# microcontroller.net
KiCad netlist of a schematic drawn in Altium Designer
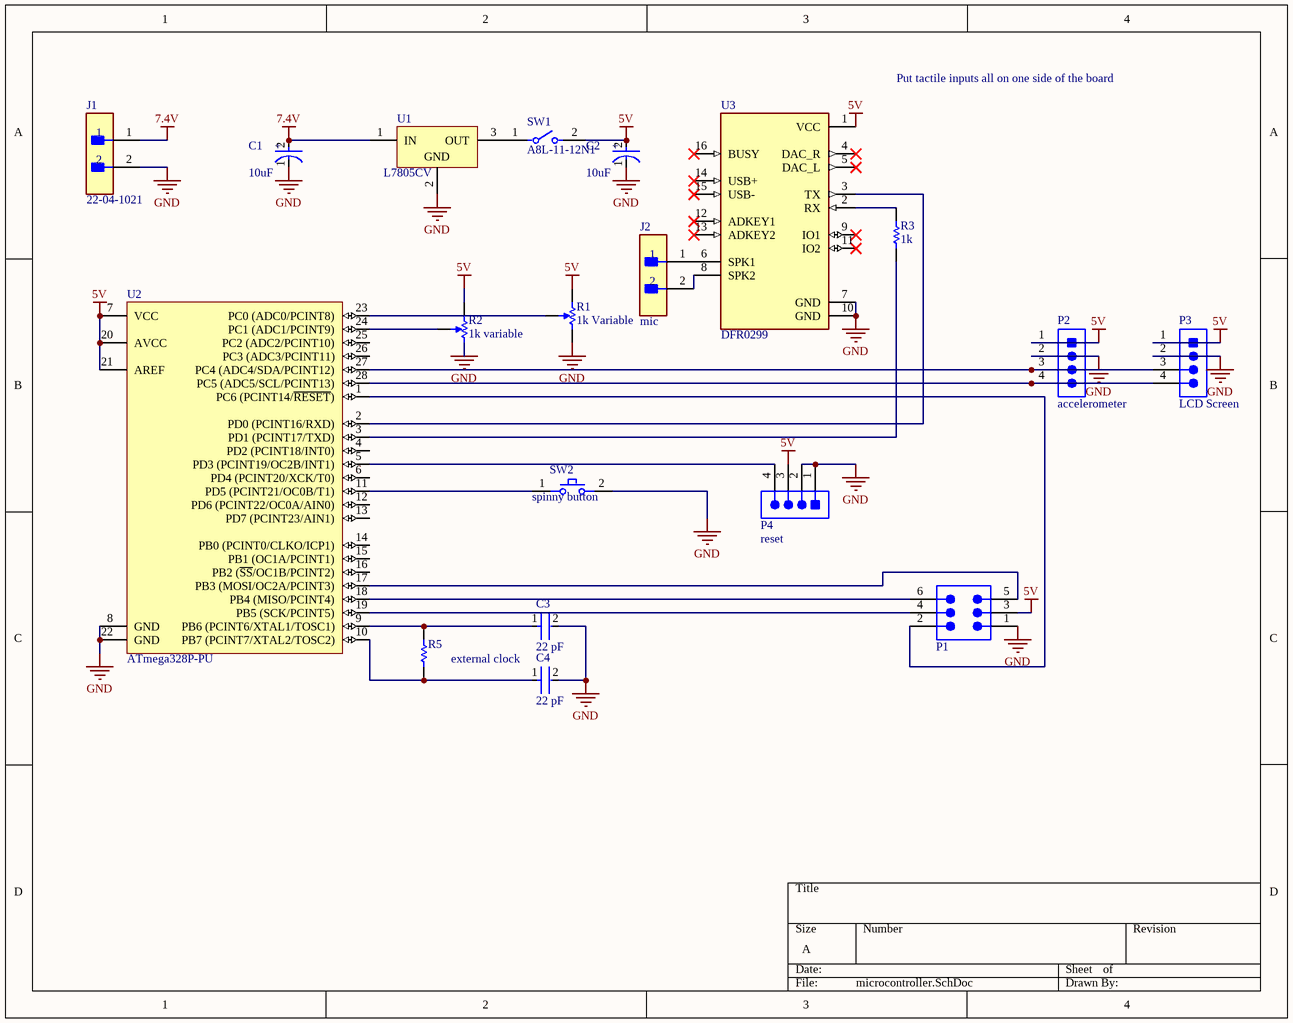
[diagram p0: microcontroller.SchDoc]

(export (version "E")
  (design (tool "Eeschema 10.0.6"))
  (components
    (comp (ref "C1")
      (value "10uF")
      (footprint "FP-RAD-TH-D_16_0_5-L_15_1-MFG")
      (description "Aluminum Electrolytic Capacitors (Radial Lead Type) AEC-Q200 Qualified 330uF ±20% 50V")
      (fields (field (name "TOLERANCE") "20%"))
      (libsource (lib "Altium Content Vault") (part "a00bbbee19879c290e62620ae7e47b1"))
    )
    (comp (ref "C2")
      (value "10uF")
      (footprint "FP-RAD-TH-D_16_0_5-L_15_1-MFG")
      (description "Aluminum Electrolytic Capacitors (Radial Lead Type) AEC-Q200 Qualified 330uF ±20% 50V")
      (fields (field (name "TOLERANCE") "20%"))
      (libsource (lib "Altium Content Vault") (part "a00bbbee19879c290e62620ae7e47b1"))
    )
    (comp (ref "C3")
      (value "22 pF")
      (footprint "FP-DE1_D9_T4_F10_d0_6-0_0-MFG")
      (description "Cap Ceramic Disc 2200pF 20% 250VAC Thru-Hole 9.0x4.0x10.0 Ammo pack")
      (fields (field (name "TOLERANCE") "20%"))
      (libsource (lib "Altium Content Vault") (part "11868f565c42a9108669ba33697ecf6"))
    )
    (comp (ref "C4")
      (value "22 pF")
      (footprint "FP-DE1_D9_T4_F10_d0_6-0_0-MFG")
      (description "Cap Ceramic Disc 2200pF 20% 250VAC Thru-Hole 9.0x4.0x10.0 Ammo pack")
      (fields (field (name "TOLERANCE") "20%"))
      (libsource (lib "Altium Content Vault") (part "11868f565c42a9108669ba33697ecf6"))
    )
    (comp (ref "J1")
      (value "22-04-1021")
      (footprint "FP-22-04-1021-MFG")
      (description "CONN HEADER VERT 2POS 2.5MM")
      (libsource (lib "Altium Content Vault") (part "3bc925449376181038e59eaffc5286c"))
    )
    (comp (ref "J2")
      (value "mic")
      (footprint "FP-22-04-1021-MFG")
      (description "CONN HEADER VERT 2POS 2.5MM")
      (libsource (lib "Altium Content Vault") (part "3bc925449376181038e59eaffc5286c"))
    )
    (comp (ref "P1")
      (value "61200621621")
      (footprint "61200621621")
      (description "WR-BHD Male Box Header, THT Straight, pitch 2.54mm, 2 row, 6 pin")
      (fields (field (name "MANUFACTURER") "Wurth Elektronik"))
      (libsource (lib "Altium_WR-BHD_rev22c") (part "61200621621"))
    )
    (comp (ref "P2")
      (value "accelerometer")
      (footprint "MOLX-22-27-2041_V")
      (description "Male Header, Pitch 2.54 mm, 1 x 4 Position, Height 11.7 mm, Tail Length 3.56 mm, RoHS, Bulk")
      (fields (field (name "MANUFACTURER") "Molex"))
      (libsource (lib "Altium Content Vault") (part "CN-1P-M-R4"))
    )
    (comp (ref "P3")
      (value "LCD Screen")
      (footprint "MOLX-22-27-2041_V")
      (description "Male Header, Pitch 2.54 mm, 1 x 4 Position, Height 11.7 mm, Tail Length 3.56 mm, RoHS, Bulk")
      (fields (field (name "MANUFACTURER") "Molex"))
      (libsource (lib "Altium Content Vault") (part "CN-1P-M-R4"))
    )
    (comp (ref "P4")
      (value "reset")
      (footprint "MOLX-22-27-2041_V")
      (description "Male Header, Pitch 2.54 mm, 1 x 4 Position, Height 11.7 mm, Tail Length 3.56 mm, RoHS, Bulk")
      (fields (field (name "MANUFACTURER") "Molex"))
      (libsource (lib "") (part "CN-1P-M-R4_1"))
    )
    (comp (ref "R1")
      (value "1k Variable")
      (footprint "BIT-93PR1KLF")
      (fields (field (name "MANUFACTURER") "BI Technologies"))
      (libsource (lib "Altium Content Vault") (part "RES-ADJ-3_A"))
    )
    (comp (ref "R2")
      (value "1k variable")
      (footprint "BIT-93PR1KLF")
      (fields (field (name "MANUFACTURER") "BI Technologies"))
      (libsource (lib "Altium Content Vault") (part "RES-ADJ-3_A"))
    )
    (comp (ref "R3")
      (value "1k")
      (footprint "RESA60-630X240")
      (description "Axial Resistor, 1 KOhm, +/- 1%, 250 mW, -55 to 155 degC, 2-Pin THD, RoHS, Bulk")
      (fields (field (name "TOLERANCE") "1%"))
      (libsource (lib "Altium Content Vault") (part "RES-2"))
    )
    (comp (ref "R5")
      (value "external clock")
      (footprint "RESA60-630X240")
      (description "Axial Resistor, 1 KOhm, +/- 1%, 250 mW, -55 to 155 degC, 2-Pin THD, RoHS, Bulk")
      (fields (field (name "TOLERANCE") "1%"))
      (libsource (lib "Altium Content Vault") (part "RES-2"))
    )
    (comp (ref "SW1")
      (value "A8L-11-12N1")
      (footprint "FP-A8L-11-12N1-MFG")
      (description "SWITCH ROCKER SPST 10A 125V")
      (libsource (lib "Altium Content Vault") (part "bb27bde45df87f1f469753f287ef5ae"))
    )
    (comp (ref "SW2")
      (value "spinny button")
      (footprint "FP-B3AL-1003P-MFG")
      (description "SWITCH TACTILE SPST-NO 0.05A 16V")
      (libsource (lib "Altium Content Vault") (part "69e8347f6a24c021ef43a914a4df441"))
    )
    (comp (ref "U1")
      (value "L7805CV")
      (footprint "TO220")
      (description "Positive Voltage Regulator, 5V, 3-Pin TO-220")
      (libsource (lib "Altium Content Vault") (part "PM-REG-L4940-SIL3"))
    )
    (comp (ref "U2")
      (value "ATmega328P-PU")
      (footprint "28P3")
      (libsource (lib "Altium Content Vault") (part "MC-8B-ATM48-IL28"))
    )
    (comp (ref "U3")
      (value "DFR0299")
      (footprint "MODULE_DFR0299")
      (description "Dfplayer - a Mini Mp3 Player")
      (libsource (lib "DFR0299") (part "DFR0299"))
    )
  )
  (nets
    (net (code "1") (name "5V") (class "Default")
      (node (ref "C2") (pin "2") (pinfunction "A_2") (pintype "passive"))
      (node (ref "P1") (pin "3") (pinfunction "3_3") (pintype "passive"))
      (node (ref "P2") (pin "1") (pinfunction "1_1") (pintype "passive"))
      (node (ref "P3") (pin "1") (pinfunction "1_1") (pintype "passive"))
      (node (ref "P4") (pin "3") (pinfunction "3_3") (pintype "passive"))
      (node (ref "R1") (pin "1") (pinfunction "1_1") (pintype "passive"))
      (node (ref "R2") (pin "1") (pinfunction "1_1") (pintype "passive"))
      (node (ref "SW1") (pin "2") (pinfunction "2_2") (pintype "passive"))
      (node (ref "U2") (pin "20") (pinfunction "AVCC_20") (pintype "power_in"))
      (node (ref "U2") (pin "21") (pinfunction "AREF_21") (pintype "power_in"))
      (node (ref "U2") (pin "7") (pinfunction "VCC_7") (pintype "power_in"))
      (node (ref "U3") (pin "1") (pinfunction "VCC_1") (pintype "power_in"))
    )
    (net (code "2") (name "7.4V") (class "Default")
      (node (ref "C1") (pin "2") (pinfunction "A_2") (pintype "passive"))
      (node (ref "J1") (pin "1") (pinfunction "1_1") (pintype "passive"))
      (node (ref "U1") (pin "1") (pinfunction "IN_1") (pintype "power_in"))
    )
    (net (code "3") (name "GND") (class "Default")
      (node (ref "C1") (pin "1") (pinfunction "C_1") (pintype "passive"))
      (node (ref "C2") (pin "1") (pinfunction "C_1") (pintype "passive"))
      (node (ref "C3") (pin "2") (pinfunction "2_2") (pintype "passive"))
      (node (ref "C4") (pin "2") (pinfunction "2_2") (pintype "passive"))
      (node (ref "J1") (pin "2") (pinfunction "2_2") (pintype "passive"))
      (node (ref "P1") (pin "1") (pinfunction "1_1") (pintype "passive"))
      (node (ref "P2") (pin "2") (pinfunction "2_2") (pintype "passive"))
      (node (ref "P3") (pin "2") (pinfunction "2_2") (pintype "passive"))
      (node (ref "P4") (pin "1") (pinfunction "1_1") (pintype "passive"))
      (node (ref "P4") (pin "2") (pinfunction "2_2") (pintype "passive"))
      (node (ref "R1") (pin "3") (pinfunction "3_3") (pintype "passive"))
      (node (ref "R2") (pin "3") (pinfunction "3_3") (pintype "passive"))
      (node (ref "SW2") (pin "2") (pinfunction "2_2") (pintype "passive"))
      (node (ref "U1") (pin "2") (pinfunction "GND_2") (pintype "power_in"))
      (node (ref "U2") (pin "22") (pinfunction "GND_22") (pintype "power_in"))
      (node (ref "U2") (pin "8") (pinfunction "GND_8") (pintype "power_in"))
      (node (ref "U3") (pin "10") (pinfunction "GND_10") (pintype "power_in"))
      (node (ref "U3") (pin "7") (pinfunction "GND_7") (pintype "power_in"))
    )
    (net (code "4") (name "Net-(U1-OUT)") (class "Default")
      (node (ref "SW1") (pin "1") (pinfunction "1_1") (pintype "passive"))
      (node (ref "U1") (pin "3") (pinfunction "OUT_3") (pintype "power_in"))
    )
    (net (code "5") (name "Net-(U2-PB3_(MOSI{slash}OC2A{slash}PCINT3))") (class "Default")
      (node (ref "P1") (pin "5") (pinfunction "5_5") (pintype "passive"))
      (node (ref "U2") (pin "17") (pinfunction "PB3_(MOSI/OC2A/PCINT3)_17") (pintype "bidirectional"))
    )
    (net (code "6") (name "Net-(U2-PB4_(MISO{slash}PCINT4))") (class "Default")
      (node (ref "P1") (pin "6") (pinfunction "6_6") (pintype "passive"))
      (node (ref "U2") (pin "18") (pinfunction "PB4_(MISO/PCINT4)_18") (pintype "bidirectional"))
    )
    (net (code "7") (name "Net-(U2-PB5_(SCK{slash}PCINT5))") (class "Default")
      (node (ref "P1") (pin "4") (pinfunction "4_4") (pintype "passive"))
      (node (ref "U2") (pin "19") (pinfunction "PB5_(SCK/PCINT5)_19") (pintype "bidirectional"))
    )
    (net (code "8") (name "Net-(U2-PB6_(PCINT6{slash}XTAL1{slash}TOSC1))") (class "Default")
      (node (ref "C3") (pin "1") (pinfunction "1_1") (pintype "passive"))
      (node (ref "R5") (pin "2") (pinfunction "2_2") (pintype "passive"))
      (node (ref "U2") (pin "9") (pinfunction "PB6_(PCINT6/XTAL1/TOSC1)_9") (pintype "bidirectional"))
    )
    (net (code "9") (name "Net-(U2-PB7_(PCINT7{slash}XTAL2{slash}TOSC2))") (class "Default")
      (node (ref "C4") (pin "1") (pinfunction "1_1") (pintype "passive"))
      (node (ref "R5") (pin "1") (pinfunction "1_1") (pintype "passive"))
      (node (ref "U2") (pin "10") (pinfunction "PB7_(PCINT7/XTAL2/TOSC2)_10") (pintype "bidirectional"))
    )
    (net (code "10") (name "Net-(U2-PC0_(ADC0{slash}PCINT8))") (class "Default")
      (node (ref "R1") (pin "2") (pinfunction "2_2") (pintype "passive"))
      (node (ref "U2") (pin "23") (pinfunction "PC0_(ADC0/PCINT8)_23") (pintype "bidirectional"))
    )
    (net (code "11") (name "Net-(U2-PC1_(ADC1{slash}PCINT9))") (class "Default")
      (node (ref "R2") (pin "2") (pinfunction "2_2") (pintype "passive"))
      (node (ref "U2") (pin "24") (pinfunction "PC1_(ADC1/PCINT9)_24") (pintype "bidirectional"))
    )
    (net (code "12") (name "Net-(U2-PC4_(ADC4{slash}SDA{slash}PCINT12))") (class "Default")
      (node (ref "P2") (pin "3") (pinfunction "3_3") (pintype "passive"))
      (node (ref "P3") (pin "3") (pinfunction "3_3") (pintype "passive"))
      (node (ref "U2") (pin "27") (pinfunction "PC4_(ADC4/SDA/PCINT12)_27") (pintype "bidirectional"))
    )
    (net (code "13") (name "Net-(U2-PC5_(ADC5{slash}SCL{slash}PCINT13))") (class "Default")
      (node (ref "P2") (pin "4") (pinfunction "4_4") (pintype "passive"))
      (node (ref "P3") (pin "4") (pinfunction "4_4") (pintype "passive"))
      (node (ref "U2") (pin "28") (pinfunction "PC5_(ADC5/SCL/PCINT13)_28") (pintype "bidirectional"))
    )
    (net (code "14") (name "Net-(U2-PC6_(PCINT14{slash}~{RESET}))") (class "Default")
      (node (ref "P1") (pin "2") (pinfunction "2_2") (pintype "passive"))
      (node (ref "U2") (pin "1") (pinfunction "PC6_(PCINT14/~{RESET})_1") (pintype "bidirectional"))
    )
    (net (code "15") (name "Net-(U2-PD0_(PCINT16{slash}RXD))") (class "Default")
      (node (ref "U2") (pin "2") (pinfunction "PD0_(PCINT16/RXD)_2") (pintype "bidirectional"))
      (node (ref "U3") (pin "3") (pinfunction "TX_3") (pintype "output"))
    )
    (net (code "16") (name "Net-(U2-PD1_(PCINT17{slash}TXD))") (class "Default")
      (node (ref "R3") (pin "1") (pinfunction "1_1") (pintype "passive"))
      (node (ref "U2") (pin "3") (pinfunction "PD1_(PCINT17/TXD)_3") (pintype "bidirectional"))
    )
    (net (code "17") (name "Net-(U2-PD3_(PCINT19{slash}OC2B{slash}INT1))") (class "Default")
      (node (ref "P4") (pin "4") (pinfunction "4_4") (pintype "passive"))
      (node (ref "U2") (pin "5") (pinfunction "PD3_(PCINT19/OC2B/INT1)_5") (pintype "bidirectional"))
    )
    (net (code "18") (name "Net-(U2-PD5_(PCINT21{slash}OC0B{slash}T1))") (class "Default")
      (node (ref "SW2") (pin "1") (pinfunction "1_1") (pintype "passive"))
      (node (ref "U2") (pin "11") (pinfunction "PD5_(PCINT21/OC0B/T1)_11") (pintype "bidirectional"))
    )
    (net (code "19") (name "Net-(U3-RX)") (class "Default")
      (node (ref "R3") (pin "2") (pinfunction "2_2") (pintype "passive"))
      (node (ref "U3") (pin "2") (pinfunction "RX_2") (pintype "input"))
    )
    (net (code "20") (name "Net-(U3-SPK1)") (class "Default")
      (node (ref "J2") (pin "1") (pinfunction "1_1") (pintype "passive"))
      (node (ref "U3") (pin "6") (pinfunction "SPK1_6") (pintype "passive"))
    )
    (net (code "21") (name "Net-(U3-SPK2)") (class "Default")
      (node (ref "J2") (pin "2") (pinfunction "2_2") (pintype "passive"))
      (node (ref "U3") (pin "8") (pinfunction "SPK2_8") (pintype "passive"))
    )
    (net (code "22") (name "unconnected-(U2-PB0_(PCINT0{slash}CLKO{slash}ICP1)-Pad14)") (class "Default")
      (node (ref "U2") (pin "14") (pinfunction "PB0_(PCINT0/CLKO/ICP1)_14") (pintype "bidirectional"))
    )
    (net (code "23") (name "unconnected-(U2-PB1_(OC1A{slash}PCINT1)-Pad15)") (class "Default")
      (node (ref "U2") (pin "15") (pinfunction "PB1_(OC1A/PCINT1)_15") (pintype "bidirectional"))
    )
    (net (code "24") (name "unconnected-(U2-PB2_(~{SS}{slash}OC1B{slash}PCINT2)-Pad16)") (class "Default")
      (node (ref "U2") (pin "16") (pinfunction "PB2_(~{SS}/OC1B/PCINT2)_16") (pintype "bidirectional"))
    )
    (net (code "25") (name "unconnected-(U2-PC2_(ADC2{slash}PCINT10)-Pad25)") (class "Default")
      (node (ref "U2") (pin "25") (pinfunction "PC2_(ADC2/PCINT10)_25") (pintype "bidirectional"))
    )
    (net (code "26") (name "unconnected-(U2-PC3_(ADC3{slash}PCINT11)-Pad26)") (class "Default")
      (node (ref "U2") (pin "26") (pinfunction "PC3_(ADC3/PCINT11)_26") (pintype "bidirectional"))
    )
    (net (code "27") (name "unconnected-(U2-PD2_(PCINT18{slash}INT0)-Pad4)") (class "Default")
      (node (ref "U2") (pin "4") (pinfunction "PD2_(PCINT18/INT0)_4") (pintype "bidirectional"))
    )
    (net (code "28") (name "unconnected-(U2-PD4_(PCINT20{slash}XCK{slash}T0)-Pad6)") (class "Default")
      (node (ref "U2") (pin "6") (pinfunction "PD4_(PCINT20/XCK/T0)_6") (pintype "bidirectional"))
    )
    (net (code "29") (name "unconnected-(U2-PD6_(PCINT22{slash}OC0A{slash}AIN0)-Pad12)") (class "Default")
      (node (ref "U2") (pin "12") (pinfunction "PD6_(PCINT22/OC0A/AIN0)_12") (pintype "bidirectional"))
    )
    (net (code "30") (name "unconnected-(U2-PD7_(PCINT23{slash}AIN1)-Pad13)") (class "Default")
      (node (ref "U2") (pin "13") (pinfunction "PD7_(PCINT23/AIN1)_13") (pintype "bidirectional"))
    )
    (net (code "31") (name "unconnected-(U3-ADKEY1-Pad12)") (class "Default")
      (node (ref "U3") (pin "12") (pinfunction "ADKEY1_12") (pintype "input+no_connect"))
    )
    (net (code "32") (name "unconnected-(U3-ADKEY2-Pad13)") (class "Default")
      (node (ref "U3") (pin "13") (pinfunction "ADKEY2_13") (pintype "input+no_connect"))
    )
    (net (code "33") (name "unconnected-(U3-BUSY-Pad16)") (class "Default")
      (node (ref "U3") (pin "16") (pinfunction "BUSY_16") (pintype "input+no_connect"))
    )
    (net (code "34") (name "unconnected-(U3-DAC_L-Pad5)") (class "Default")
      (node (ref "U3") (pin "5") (pinfunction "DAC_L_5") (pintype "output+no_connect"))
    )
    (net (code "35") (name "unconnected-(U3-DAC_R-Pad4)") (class "Default")
      (node (ref "U3") (pin "4") (pinfunction "DAC_R_4") (pintype "output+no_connect"))
    )
    (net (code "36") (name "unconnected-(U3-IO1-Pad9)") (class "Default")
      (node (ref "U3") (pin "9") (pinfunction "IO1_9") (pintype "bidirectional+no_connect"))
    )
    (net (code "37") (name "unconnected-(U3-IO2-Pad11)") (class "Default")
      (node (ref "U3") (pin "11") (pinfunction "IO2_11") (pintype "bidirectional+no_connect"))
    )
    (net (code "38") (name "unconnected-(U3-USB+-Pad14)") (class "Default")
      (node (ref "U3") (pin "14") (pinfunction "USB+_14") (pintype "input+no_connect"))
    )
    (net (code "39") (name "unconnected-(U3-USB--Pad15)") (class "Default")
      (node (ref "U3") (pin "15") (pinfunction "USB-_15") (pintype "input+no_connect"))
    )
  )
)
